# irs-lsm303d-v2.net
KiCad netlist of a schematic drawn in EAGLE
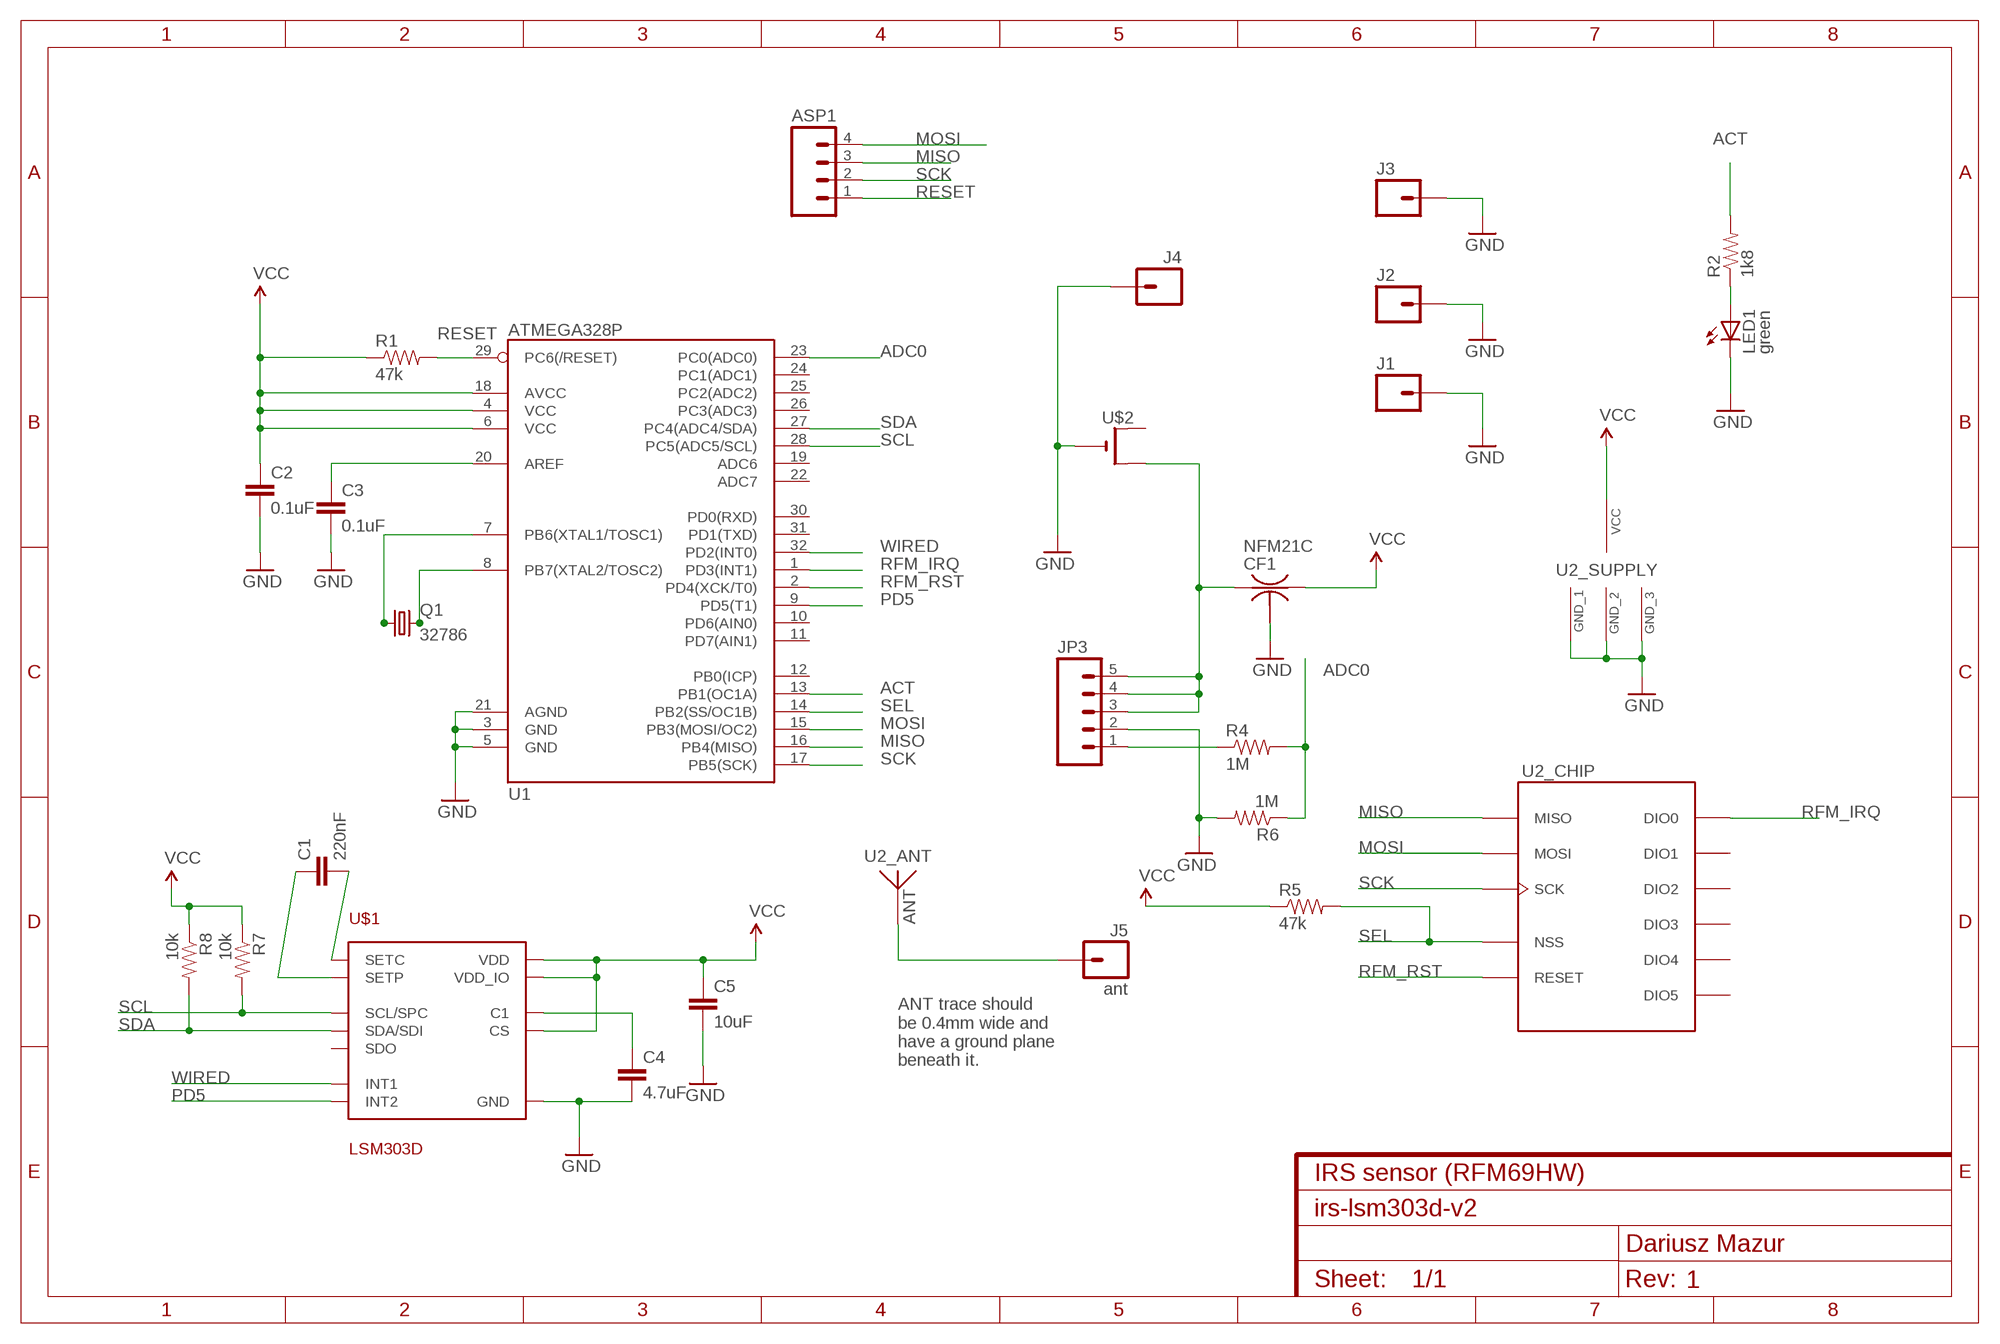
[diagram p0: schematic, sheet 1]

(export (version "E")
  (design (tool "Eeschema 10.0.6"))
  (components
    (comp (ref "ASP1")
      (value "M04NO_SILK_ALL_ROUND")
      (footprint "eagle-import:1X04_NO_SILK_ALL_ROUND")
      (libsource (lib "eagle-import") (part "M04NO_SILK_ALL_ROUND"))
    )
    (comp (ref "C1")
      (value "220nF")
      (footprint "eagle-import:C0603K")
      (libsource (lib "eagle-import") (part "C-EUC0603K"))
    )
    (comp (ref "C2")
      (value "0.1uF")
      (footprint "eagle-import:C0603K")
      (libsource (lib "eagle-import") (part "C-EUC0603K"))
    )
    (comp (ref "C3")
      (value "0.1uF")
      (footprint "eagle-import:0603-CAP")
      (libsource (lib "eagle-import") (part "0.1UF-25V(+80/-20%)(0603)"))
    )
    (comp (ref "C4")
      (value "4.7uF")
      (footprint "eagle-import:C0603K")
      (libsource (lib "eagle-import") (part "C-EUC0603K"))
    )
    (comp (ref "C5")
      (value "10uF")
      (footprint "eagle-import:0805-CAP")
      (libsource (lib "eagle-import") (part "10UF10V10%(0805)"))
    )
    (comp (ref "CF1")
      (value "NFM21C")
      (footprint "eagle-import:NFM21C")
      (fields (field (name "MPN") "NFM21CC102R1H3D"))
      (libsource (lib "eagle-import") (part "NFM21C"))
    )
    (comp (ref "J1")
      (value "M01PTH_NO_SILK_YES_STOP")
      (footprint "eagle-import:1X01_NO_SILK")
      (libsource (lib "eagle-import") (part "M01PTH_NO_SILK_YES_STOP"))
    )
    (comp (ref "J2")
      (value "M01PTH_NO_SILK_YES_STOP")
      (footprint "eagle-import:1X01_NO_SILK")
      (libsource (lib "eagle-import") (part "M01PTH_NO_SILK_YES_STOP"))
    )
    (comp (ref "J3")
      (value "M01PTH_NO_SILK_YES_STOP")
      (footprint "eagle-import:1X01_NO_SILK")
      (libsource (lib "eagle-import") (part "M01PTH_NO_SILK_YES_STOP"))
    )
    (comp (ref "J4")
      (value "M01SNAP-FEMALE")
      (footprint "eagle-import:SNAP-FEMALE")
      (libsource (lib "eagle-import") (part "M01SNAP-FEMALE"))
    )
    (comp (ref "J5")
      (value "ant")
      (footprint "eagle-import:1X01_NO_SILK")
      (libsource (lib "eagle-import") (part "M01PTH_NO_SILK_YES_STOP"))
    )
    (comp (ref "JP3")
      (value "M05NO_SILK")
      (footprint "eagle-import:1X05_NO_SILK")
      (libsource (lib "eagle-import") (part "M05NO_SILK"))
    )
    (comp (ref "LED1")
      (value "green")
      (footprint "eagle-import:LED-0603")
      (libsource (lib "eagle-import") (part "LED0603"))
    )
    (comp (ref "Q1")
      (value "32786")
      (footprint "eagle-import:MC-306")
      (fields (field (name "MPN") "MC-306 60.0KHZ  100PPM ,12.5PF"))
      (libsource (lib "eagle-import") (part "MC-306"))
    )
    (comp (ref "R1")
      (value "47k")
      (footprint "eagle-import:0603-RES")
      (libsource (lib "eagle-import") (part "RESISTOR0603-RES"))
    )
    (comp (ref "R2")
      (value "1k8")
      (footprint "eagle-import:0603-RES")
      (libsource (lib "eagle-import") (part "RESISTOR0603-RES"))
    )
    (comp (ref "R4")
      (value "1M")
      (footprint "eagle-import:0603-RES")
      (libsource (lib "eagle-import") (part "RESISTOR0603-RES"))
    )
    (comp (ref "R5")
      (value "47k")
      (footprint "eagle-import:0603-RES")
      (libsource (lib "eagle-import") (part "RESISTOR0603-RES"))
    )
    (comp (ref "R6")
      (value "1M")
      (footprint "eagle-import:0603-RES")
      (libsource (lib "eagle-import") (part "RESISTOR0603-RES"))
    )
    (comp (ref "R7")
      (value "10k")
      (footprint "eagle-import:0603-RES")
      (libsource (lib "eagle-import") (part "RESISTOR0603-RES"))
    )
    (comp (ref "R8")
      (value "10k")
      (footprint "eagle-import:0603-RES")
      (libsource (lib "eagle-import") (part "RESISTOR0603-RES"))
    )
    (comp (ref "U$1")
      (value "LSM303D")
      (footprint "eagle-import:LGA16-3MM")
      (libsource (lib "eagle-import") (part "LSM303D"))
    )
    (comp (ref "U$2")
      (value "CR2032THM")
      (footprint "eagle-import:CR2032-THRU")
      (libsource (lib "eagle-import") (part "CR2032THM"))
    )
    (comp (ref "U1")
      (value "ATMEGA328P")
      (footprint "eagle-import:TQFP32-08")
      (libsource (lib "eagle-import") (part "ATMEGA328_SMT"))
    )
    (comp (ref "U2")
      (value "RFM69HCW-S2")
      (footprint "eagle-import:HOPE-RF-16")
      (libsource (lib "eagle-import") (part "RFM69HCW-S2"))
    )
  )
  (nets
    (net (code "1") (name "/ACT") (class "Default")
      (node (ref "R2") (pin "2") (pinfunction "2_2") (pintype "passive"))
      (node (ref "U1") (pin "13") (pinfunction "PB1(OC1A)_13") (pintype "bidirectional"))
    )
    (net (code "2") (name "/ADC0") (class "Default")
      (node (ref "R4") (pin "2") (pinfunction "2_2") (pintype "passive"))
      (node (ref "R6") (pin "1") (pinfunction "1_1") (pintype "passive"))
      (node (ref "U1") (pin "23") (pinfunction "PC0(ADC0)_23") (pintype "bidirectional"))
    )
    (net (code "3") (name "/MISO") (class "Default")
      (node (ref "ASP1") (pin "3") (pinfunction "3_3") (pintype "passive"))
      (node (ref "U1") (pin "16") (pinfunction "PB4(MISO)_16") (pintype "bidirectional"))
      (node (ref "U2") (pin "MISO") (pinfunction "MISO_MISO") (pintype "input"))
    )
    (net (code "4") (name "/MOSI") (class "Default")
      (node (ref "ASP1") (pin "4") (pinfunction "4_4") (pintype "passive"))
      (node (ref "U1") (pin "15") (pinfunction "PB3(MOSI/OC2)_15") (pintype "bidirectional"))
      (node (ref "U2") (pin "MOSI") (pinfunction "MOSI_MOSI") (pintype "output"))
    )
    (net (code "5") (name "/PD5") (class "Default")
      (node (ref "U$1") (pin "9") (pinfunction "INT2_9") (pintype "bidirectional"))
      (node (ref "U1") (pin "9") (pinfunction "PD5(T1)_9") (pintype "bidirectional"))
    )
    (net (code "6") (name "/RESET") (class "Default")
      (node (ref "ASP1") (pin "1") (pinfunction "1_1") (pintype "passive"))
      (node (ref "R1") (pin "2") (pinfunction "2_2") (pintype "passive"))
      (node (ref "U1") (pin "29") (pinfunction "PC6(/RESET)_29") (pintype "bidirectional"))
    )
    (net (code "7") (name "/RFM_IRQ") (class "Default")
      (node (ref "U1") (pin "1") (pinfunction "PD3(INT1)_1") (pintype "bidirectional"))
      (node (ref "U2") (pin "DIO0") (pinfunction "DIO0_DIO0") (pintype "bidirectional"))
    )
    (net (code "8") (name "/RFM_RST") (class "Default")
      (node (ref "U1") (pin "2") (pinfunction "PD4(XCK/T0)_2") (pintype "bidirectional"))
      (node (ref "U2") (pin "RESET") (pinfunction "RESET_RESET") (pintype "bidirectional"))
    )
    (net (code "9") (name "/SCK") (class "Default")
      (node (ref "ASP1") (pin "2") (pinfunction "2_2") (pintype "passive"))
      (node (ref "U1") (pin "17") (pinfunction "PB5(SCK)_17") (pintype "bidirectional"))
      (node (ref "U2") (pin "SCK") (pinfunction "SCK_SCK") (pintype "input"))
    )
    (net (code "10") (name "/SCL") (class "Default")
      (node (ref "R7") (pin "2") (pinfunction "2_2") (pintype "passive"))
      (node (ref "U$1") (pin "4") (pinfunction "SCL/SPC_4") (pintype "bidirectional"))
      (node (ref "U1") (pin "28") (pinfunction "PC5(ADC5/SCL)_28") (pintype "bidirectional"))
    )
    (net (code "11") (name "/SDA") (class "Default")
      (node (ref "R8") (pin "2") (pinfunction "2_2") (pintype "passive"))
      (node (ref "U$1") (pin "6") (pinfunction "SDA/SDI_6") (pintype "bidirectional"))
      (node (ref "U1") (pin "27") (pinfunction "PC4(ADC4/SDA)_27") (pintype "bidirectional"))
    )
    (net (code "12") (name "/SEL") (class "Default")
      (node (ref "R5") (pin "2") (pinfunction "2_2") (pintype "passive"))
      (node (ref "U1") (pin "14") (pinfunction "PB2(SS/OC1B)_14") (pintype "bidirectional"))
      (node (ref "U2") (pin "NSS") (pinfunction "NSS_NSS") (pintype "input"))
    )
    (net (code "13") (name "/WIRED") (class "Default")
      (node (ref "U$1") (pin "11") (pinfunction "INT1_11") (pintype "bidirectional"))
      (node (ref "U1") (pin "32") (pinfunction "PD2(INT0)_32") (pintype "bidirectional"))
    )
    (net (code "14") (name "GND") (class "Default")
      (node (ref "C2") (pin "2") (pinfunction "2_2") (pintype "passive"))
      (node (ref "C3") (pin "2") (pinfunction "2_2") (pintype "passive"))
      (node (ref "C4") (pin "2") (pinfunction "2_2") (pintype "passive"))
      (node (ref "C5") (pin "2") (pinfunction "2_2") (pintype "passive"))
      (node (ref "CF1") (pin "2@1") (pinfunction "2_2@1") (pintype "passive"))
      (node (ref "J1") (pin "1") (pinfunction "1_1") (pintype "passive"))
      (node (ref "J2") (pin "1") (pinfunction "1_1") (pintype "passive"))
      (node (ref "J3") (pin "1") (pinfunction "1_1") (pintype "passive"))
      (node (ref "J4") (pin "1") (pinfunction "1_1") (pintype "passive"))
      (node (ref "JP3") (pin "2") (pinfunction "2_2") (pintype "passive"))
      (node (ref "LED1") (pin "C") (pinfunction "C_C") (pintype "passive"))
      (node (ref "R6") (pin "2") (pinfunction "2_2") (pintype "passive"))
      (node (ref "U$1") (pin "10") (pinfunction "GND_10") (pintype "power_in"))
      (node (ref "U$1") (pin "12") (pinfunction "GND_12") (pintype "power_in"))
      (node (ref "U$1") (pin "13") (pinfunction "GND_13") (pintype "power_in"))
      (node (ref "U$1") (pin "16") (pinfunction "GND_16") (pintype "power_in"))
      (node (ref "U$1") (pin "5") (pinfunction "GND_5") (pintype "power_in"))
      (node (ref "U$2") (pin "-") (pinfunction "-_-") (pintype "passive"))
      (node (ref "U1") (pin "21") (pinfunction "AGND_21") (pintype "bidirectional"))
      (node (ref "U1") (pin "3") (pinfunction "GND_3") (pintype "bidirectional"))
      (node (ref "U1") (pin "5") (pinfunction "GND_5") (pintype "bidirectional"))
      (node (ref "U2") (pin "GND1") (pinfunction "GND_1_GND1") (pintype "power_in"))
      (node (ref "U2") (pin "GND2") (pinfunction "GND_2_GND2") (pintype "power_in"))
      (node (ref "U2") (pin "GND3") (pinfunction "GND_3_GND3") (pintype "power_in"))
    )
    (net (code "15") (name "Net-(J5-Pad1)") (class "Default")
      (node (ref "J5") (pin "1") (pinfunction "1_1") (pintype "passive"))
      (node (ref "U2") (pin "ANT") (pinfunction "ANT_ANT") (pintype "passive"))
    )
    (net (code "16") (name "Net-(JP3-Pad1)") (class "Default")
      (node (ref "JP3") (pin "1") (pinfunction "1_1") (pintype "passive"))
      (node (ref "R4") (pin "1") (pinfunction "1_1") (pintype "passive"))
    )
    (net (code "17") (name "Net-(LED1-PadA)") (class "Default")
      (node (ref "LED1") (pin "A") (pinfunction "A_A") (pintype "passive"))
      (node (ref "R2") (pin "1") (pinfunction "1_1") (pintype "passive"))
    )
    (net (code "18") (name "Net-(Q1-2)") (class "Default")
      (node (ref "Q1") (pin "4") (pinfunction "2_4") (pintype "passive"))
      (node (ref "U1") (pin "8") (pinfunction "PB7(XTAL2/TOSC2)_8") (pintype "bidirectional"))
    )
    (net (code "19") (name "Net-(U$1-C1)") (class "Default")
      (node (ref "C4") (pin "1") (pinfunction "1_1") (pintype "passive"))
      (node (ref "U$1") (pin "15") (pinfunction "C1_15") (pintype "bidirectional"))
    )
    (net (code "20") (name "Net-(U$1-SETC)") (class "Default")
      (node (ref "C1") (pin "2") (pinfunction "2_2") (pintype "passive"))
      (node (ref "U$1") (pin "2") (pinfunction "SETC_2") (pintype "bidirectional"))
    )
    (net (code "21") (name "Net-(U$1-SETP)") (class "Default")
      (node (ref "C1") (pin "1") (pinfunction "1_1") (pintype "passive"))
      (node (ref "U$1") (pin "3") (pinfunction "SETP_3") (pintype "bidirectional"))
    )
    (net (code "22") (name "Net-(U$2-+1)") (class "Default")
      (node (ref "CF1") (pin "1") (pinfunction "1_1") (pintype "passive"))
      (node (ref "JP3") (pin "3") (pinfunction "3_3") (pintype "passive"))
      (node (ref "JP3") (pin "4") (pinfunction "4_4") (pintype "passive"))
      (node (ref "JP3") (pin "5") (pinfunction "5_5") (pintype "passive"))
      (node (ref "U$2") (pin "+2") (pinfunction "+1_+2") (pintype "passive"))
    )
    (net (code "23") (name "Net-(U1-AREF)") (class "Default")
      (node (ref "C3") (pin "1") (pinfunction "1_1") (pintype "passive"))
      (node (ref "U1") (pin "20") (pinfunction "AREF_20") (pintype "bidirectional"))
    )
    (net (code "24") (name "Net-(U1-PB6(XTAL1{slash}TOSC1))") (class "Default")
      (node (ref "Q1") (pin "1") (pinfunction "1_1") (pintype "passive"))
      (node (ref "U1") (pin "7") (pinfunction "PB6(XTAL1/TOSC1)_7") (pintype "bidirectional"))
    )
    (net (code "25") (name "VCC") (class "Default")
      (node (ref "C2") (pin "1") (pinfunction "1_1") (pintype "passive"))
      (node (ref "C5") (pin "1") (pinfunction "1_1") (pintype "passive"))
      (node (ref "CF1") (pin "3") (pinfunction "3_3") (pintype "passive"))
      (node (ref "R1") (pin "1") (pinfunction "1_1") (pintype "passive"))
      (node (ref "R5") (pin "1") (pinfunction "1_1") (pintype "passive"))
      (node (ref "R7") (pin "1") (pinfunction "1_1") (pintype "passive"))
      (node (ref "R8") (pin "1") (pinfunction "1_1") (pintype "passive"))
      (node (ref "U$1") (pin "1") (pinfunction "VDD_IO_1") (pintype "power_in"))
      (node (ref "U$1") (pin "14") (pinfunction "VDD_14") (pintype "bidirectional"))
      (node (ref "U$1") (pin "8") (pinfunction "CS_8") (pintype "bidirectional"))
      (node (ref "U1") (pin "18") (pinfunction "AVCC_18") (pintype "bidirectional"))
      (node (ref "U1") (pin "4") (pinfunction "VCC_4") (pintype "bidirectional"))
      (node (ref "U1") (pin "6") (pinfunction "VCC_6") (pintype "bidirectional"))
      (node (ref "U2") (pin "3.3V") (pinfunction "VCC_3.3V") (pintype "power_in"))
    )
    (net (code "26") (name "unconnected-(CF1-2-Pad2@2)") (class "Default")
      (node (ref "CF1") (pin "2@2") (pinfunction "2_2@2") (pintype "passive"))
    )
    (net (code "27") (name "unconnected-(U$1-SDO-Pad7)") (class "Default")
      (node (ref "U$1") (pin "7") (pinfunction "SDO_7") (pintype "bidirectional"))
    )
    (net (code "28") (name "unconnected-(U$2-+-Pad+1)") (class "Default")
      (node (ref "U$2") (pin "+1") (pinfunction "+_+1") (pintype "passive"))
    )
    (net (code "29") (name "unconnected-(U1-ADC6-Pad19)") (class "Default")
      (node (ref "U1") (pin "19") (pinfunction "ADC6_19") (pintype "bidirectional"))
    )
    (net (code "30") (name "unconnected-(U1-ADC7-Pad22)") (class "Default")
      (node (ref "U1") (pin "22") (pinfunction "ADC7_22") (pintype "bidirectional"))
    )
    (net (code "31") (name "unconnected-(U1-PB0(ICP)-Pad12)") (class "Default")
      (node (ref "U1") (pin "12") (pinfunction "PB0(ICP)_12") (pintype "bidirectional"))
    )
    (net (code "32") (name "unconnected-(U1-PC1(ADC1)-Pad24)") (class "Default")
      (node (ref "U1") (pin "24") (pinfunction "PC1(ADC1)_24") (pintype "bidirectional"))
    )
    (net (code "33") (name "unconnected-(U1-PC2(ADC2)-Pad25)") (class "Default")
      (node (ref "U1") (pin "25") (pinfunction "PC2(ADC2)_25") (pintype "bidirectional"))
    )
    (net (code "34") (name "unconnected-(U1-PC3(ADC3)-Pad26)") (class "Default")
      (node (ref "U1") (pin "26") (pinfunction "PC3(ADC3)_26") (pintype "bidirectional"))
    )
    (net (code "35") (name "unconnected-(U1-PD0(RXD)-Pad30)") (class "Default")
      (node (ref "U1") (pin "30") (pinfunction "PD0(RXD)_30") (pintype "bidirectional"))
    )
    (net (code "36") (name "unconnected-(U1-PD1(TXD)-Pad31)") (class "Default")
      (node (ref "U1") (pin "31") (pinfunction "PD1(TXD)_31") (pintype "bidirectional"))
    )
    (net (code "37") (name "unconnected-(U1-PD6(AIN0)-Pad10)") (class "Default")
      (node (ref "U1") (pin "10") (pinfunction "PD6(AIN0)_10") (pintype "bidirectional"))
    )
    (net (code "38") (name "unconnected-(U1-PD7(AIN1)-Pad11)") (class "Default")
      (node (ref "U1") (pin "11") (pinfunction "PD7(AIN1)_11") (pintype "bidirectional"))
    )
    (net (code "39") (name "unconnected-(U2-PadDIO1)") (class "Default")
      (node (ref "U2") (pin "DIO1") (pinfunction "DIO1_DIO1") (pintype "bidirectional"))
    )
    (net (code "40") (name "unconnected-(U2-PadDIO2)") (class "Default")
      (node (ref "U2") (pin "DIO2") (pinfunction "DIO2_DIO2") (pintype "bidirectional"))
    )
    (net (code "41") (name "unconnected-(U2-PadDIO3)") (class "Default")
      (node (ref "U2") (pin "DIO3") (pinfunction "DIO3_DIO3") (pintype "bidirectional"))
    )
    (net (code "42") (name "unconnected-(U2-PadDIO4)") (class "Default")
      (node (ref "U2") (pin "DIO4") (pinfunction "DIO4_DIO4") (pintype "bidirectional"))
    )
    (net (code "43") (name "unconnected-(U2-PadDIO5)") (class "Default")
      (node (ref "U2") (pin "DIO5") (pinfunction "DIO5_DIO5") (pintype "bidirectional"))
    )
  )
)
